# ArduinoFile_Schematic.net
KiCad netlist of a schematic drawn in EasyEDA
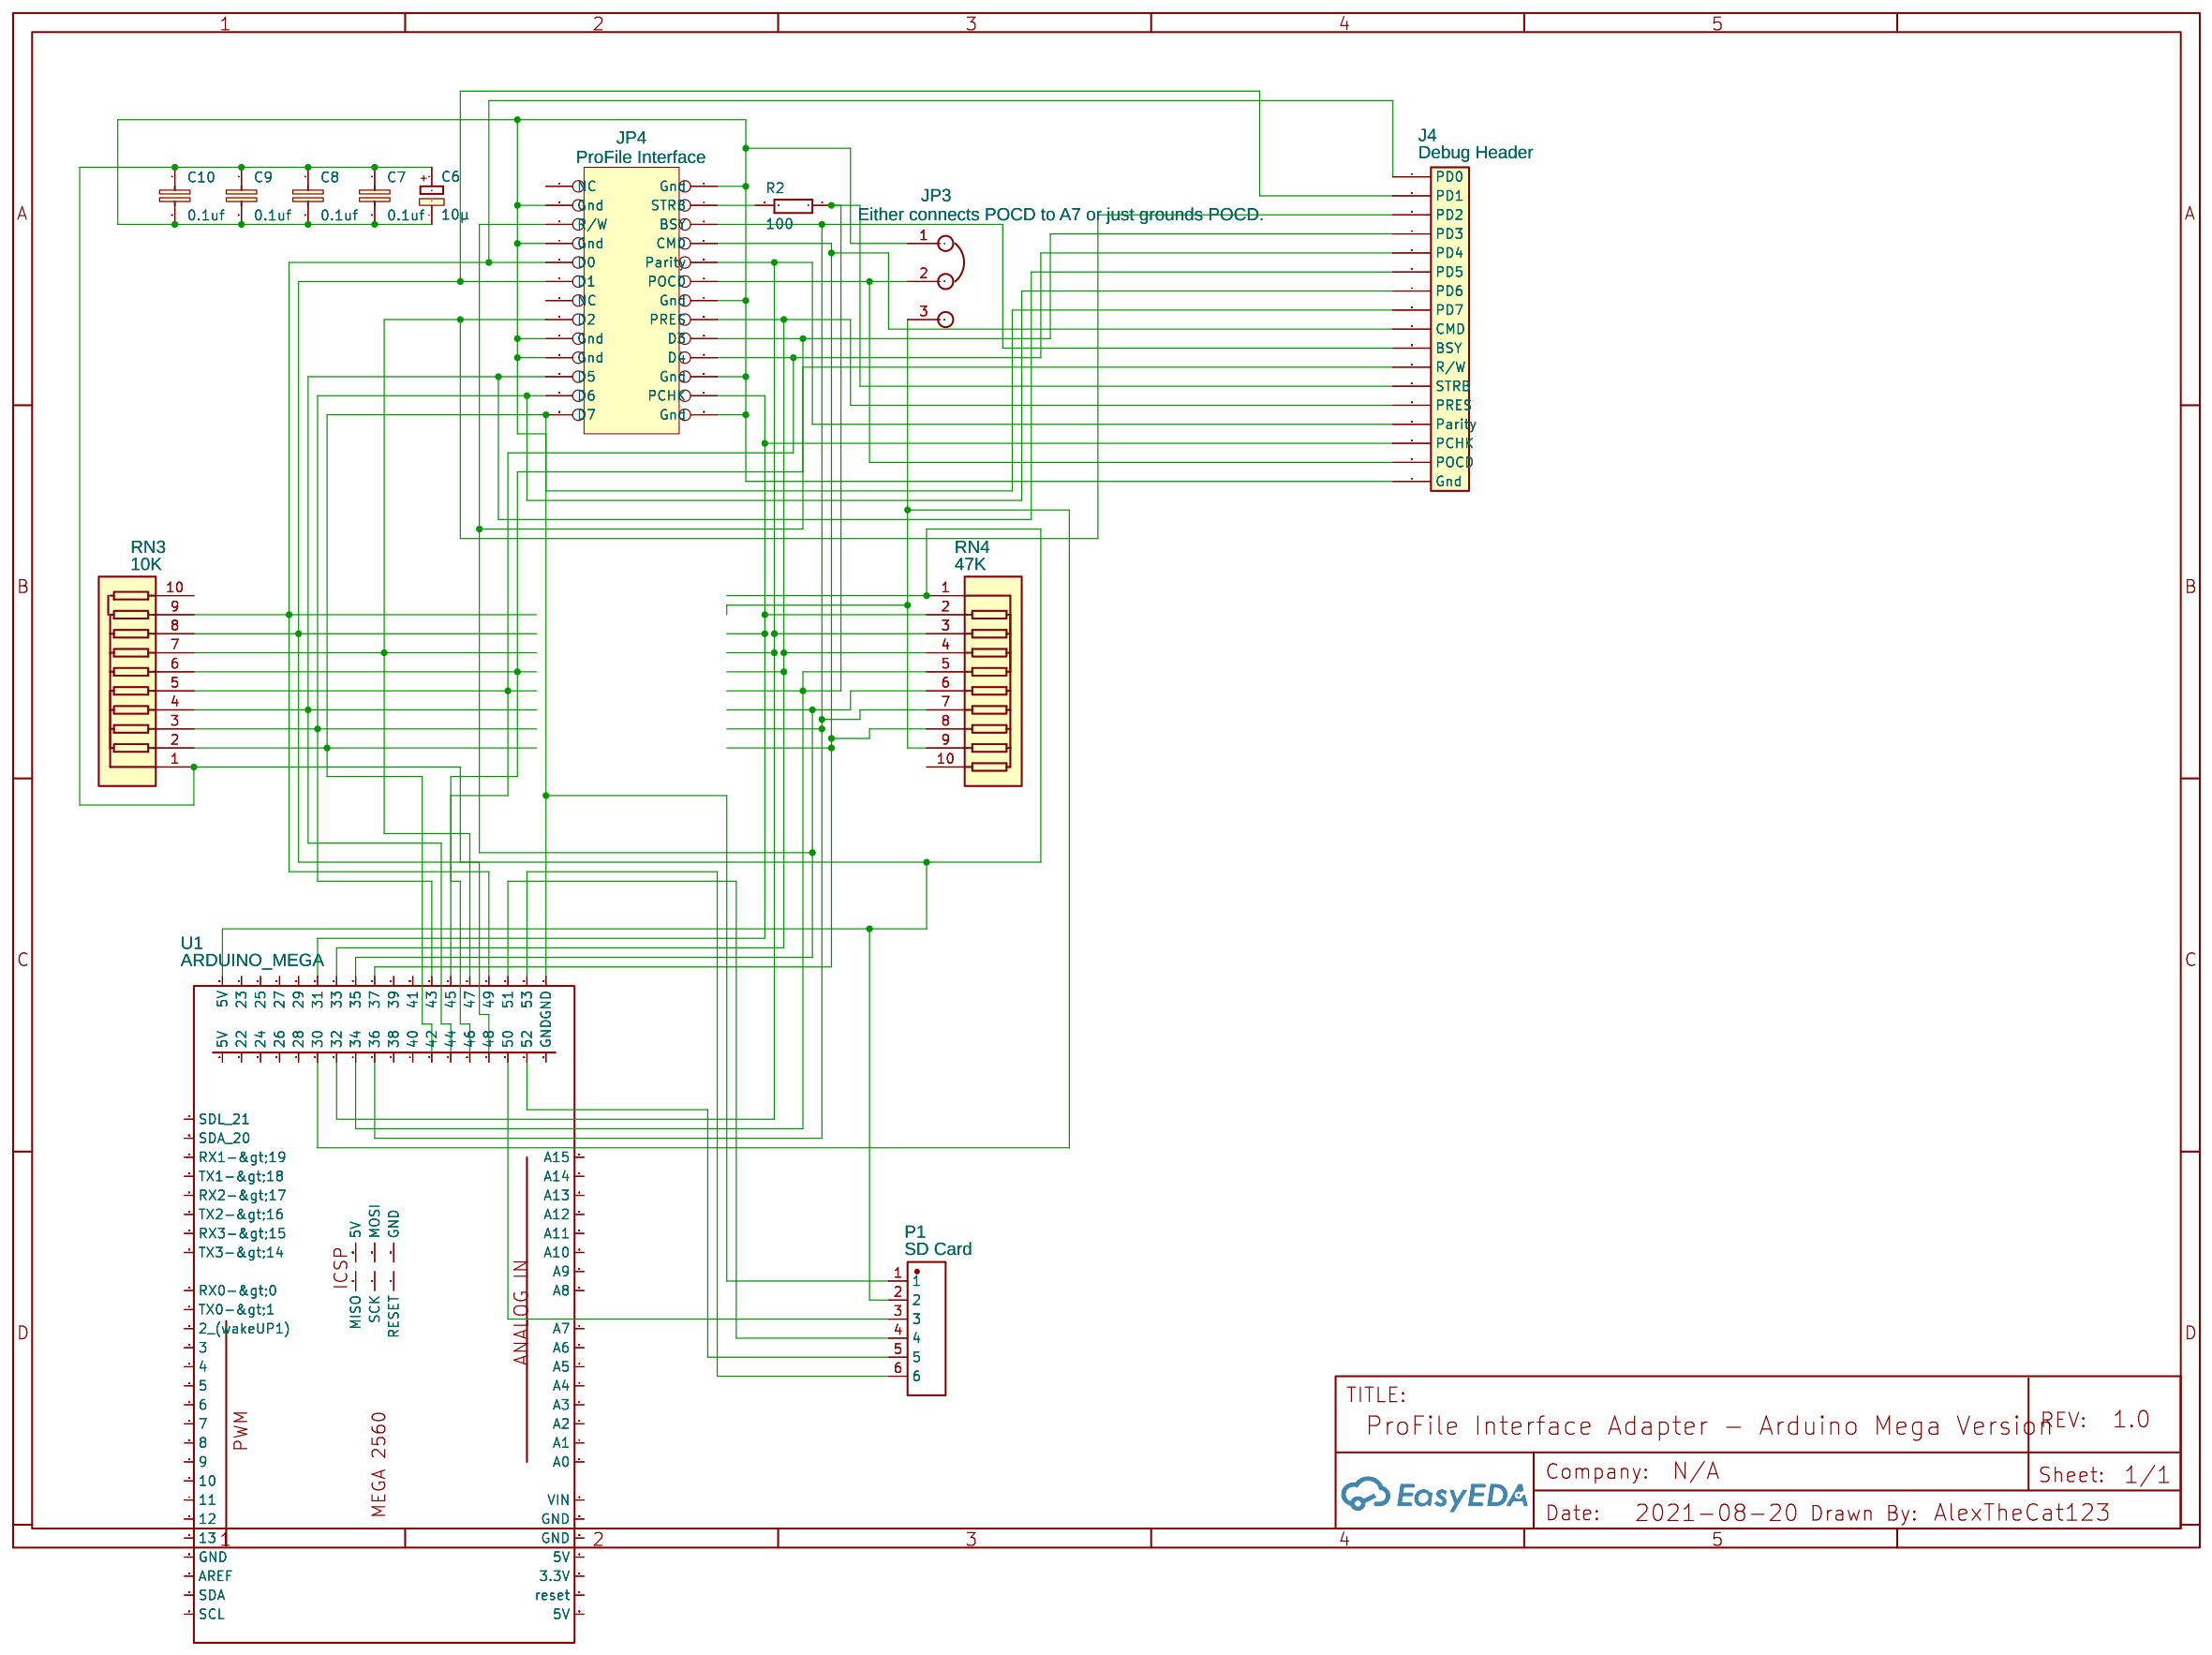
[diagram p0: schematic sheet]

(export (version "E")
  (design (tool "Eeschema 10.0.6"))
  (components
    (comp (ref "C6") (value "10µ") (libsource (lib "") (part "Unknown_220_-715")))
    (comp (ref "C7") (value "0.1uf") (libsource (lib "") (part "Unknown_190_-715")))
    (comp (ref "C8") (value "0.1uf") (libsource (lib "") (part "Unknown_155_-715")))
    (comp (ref "C9") (value "0.1uf") (libsource (lib "") (part "Unknown_120_-715")))
    (comp (ref "C10") (value "0.1uf") (libsource (lib "") (part "Unknown_85_-715")))
    (comp (ref "J4")
      (value "Debug Header")
      (fields
        (field (name "BOM_Manufacturer Part") "Header-2.54_1x17")
        (field (name "BOM_Supplier Part") "C52709")
      )
      (libsource (lib "") (part "Header-Female-2.54_1x17"))
    )
    (comp (ref "JP3")
      (value "Either connects POCD to A7 or just grounds POCD.")
      (libsource (lib "") (part "JUMPER"))
    )
    (comp (ref "JP4") (value "ProFile Interface") (libsource (lib "") (part "HEADER 13X2")))
    (comp (ref "P1")
      (value "SD Card")
      (fields
        (field (name "BOM_Manufacturer Part") "Female header 1*6p")
        (field (name "BOM_Supplier Part") "C40877")
      )
      (libsource (lib "") (part "Header-Female-2.54_1x6"))
    )
    (comp (ref "R2") (value "100") (libsource (lib "") (part "Unknown_410_-705")))
    (comp (ref "RN3")
      (value "10K")
      (fields (field (name "BOM_Manufacturer Part") "A09-202JP") (field (name "BOM_Supplier Part") "E84206"))
      (libsource (lib "") (part "1K_1"))
    )
    (comp (ref "RN4")
      (value "47K")
      (fields (field (name "BOM_Manufacturer Part") "A09-202JP") (field (name "BOM_Supplier Part") "E84206"))
      (libsource (lib "") (part "1K"))
    )
    (comp (ref "U1")
      (value "ARDUINO_MEGA")
      (fields (field (name "BOM_Manufacturer Part") "ARDUINO MEGA"))
      (libsource (lib "") (part "ARDUINO_MEGA"))
    )
  )
  (nets
    (net (code "1") (name "Net-(C10-Pad1)") (class "Default")
      (node (ref "C10") (pin "1") (pinfunction "1_1") (pintype "bidirectional"))
      (node (ref "C6") (pin "+") (pinfunction "+_+") (pintype "bidirectional"))
      (node (ref "C7") (pin "1") (pinfunction "1_1") (pintype "bidirectional"))
      (node (ref "C8") (pin "1") (pinfunction "1_1") (pintype "bidirectional"))
      (node (ref "C9") (pin "1") (pinfunction "1_1") (pintype "bidirectional"))
      (node (ref "P1") (pin "2") (pinfunction "2_2") (pintype "unspecified"))
      (node (ref "RN3") (pin "1") (pinfunction "1_1") (pintype "input"))
      (node (ref "RN4") (pin "1") (pinfunction "1_1") (pintype "input"))
      (node (ref "U1") (pin "5V..") (pinfunction "5V_5V..") (pintype "unspecified"))
    )
    (net (code "2") (name "Net-(J4-BSY)") (class "Default")
      (node (ref "J4") (pin "10") (pinfunction "BSY_10") (pintype "input"))
      (node (ref "JP4") (pin "6") (pinfunction "BSY_6") (pintype "unspecified"))
      (node (ref "RN4") (pin "7") (pinfunction "7_7") (pintype "input"))
      (node (ref "U1") (pin "43") (pinfunction "36_43") (pintype "unspecified"))
    )
    (net (code "3") (name "Net-(J4-CMD)") (class "Default")
      (node (ref "J4") (pin "9") (pinfunction "CMD_9") (pintype "input"))
      (node (ref "JP4") (pin "8") (pinfunction "CMD_8") (pintype "unspecified"))
      (node (ref "RN4") (pin "8") (pinfunction "8_8") (pintype "input"))
      (node (ref "U1") (pin "44") (pinfunction "37_44") (pintype "unspecified"))
    )
    (net (code "4") (name "Net-(J4-Gnd)") (class "Default")
      (node (ref "C10") (pin "2") (pinfunction "2_2") (pintype "bidirectional"))
      (node (ref "C6") (pin "-") (pinfunction "-_-") (pintype "bidirectional"))
      (node (ref "C7") (pin "2") (pinfunction "2_2") (pintype "bidirectional"))
      (node (ref "C8") (pin "2") (pinfunction "2_2") (pintype "bidirectional"))
      (node (ref "C9") (pin "2") (pinfunction "2_2") (pintype "bidirectional"))
      (node (ref "J4") (pin "17") (pinfunction "Gnd_17") (pintype "input"))
      (node (ref "JP3") (pin "1") (pinfunction "1_1") (pintype "unspecified"))
      (node (ref "JP4") (pin "14") (pinfunction "Gnd_14") (pintype "unspecified"))
      (node (ref "JP4") (pin "17") (pinfunction "Gnd_17") (pintype "unspecified"))
      (node (ref "JP4") (pin "19") (pinfunction "Gnd_19") (pintype "unspecified"))
      (node (ref "JP4") (pin "2") (pinfunction "Gnd_2") (pintype "unspecified"))
      (node (ref "JP4") (pin "22") (pinfunction "Gnd_22") (pintype "unspecified"))
      (node (ref "JP4") (pin "26") (pinfunction "Gnd_26") (pintype "unspecified"))
      (node (ref "JP4") (pin "3") (pinfunction "Gnd_3") (pintype "unspecified"))
      (node (ref "JP4") (pin "7") (pinfunction "Gnd_7") (pintype "unspecified"))
      (node (ref "P1") (pin "1") (pinfunction "1_1") (pintype "unspecified"))
      (node (ref "U1") (pin "GND") (pinfunction "GND_GND") (pintype "unspecified"))
    )
    (net (code "5") (name "Net-(J4-PCHK)") (class "Default")
      (node (ref "J4") (pin "15") (pinfunction "PCHK_15") (pintype "input"))
      (node (ref "JP4") (pin "24") (pinfunction "PCHK_24") (pintype "unspecified"))
      (node (ref "RN4") (pin "2") (pinfunction "2_2") (pintype "input"))
      (node (ref "U1") (pin "38") (pinfunction "31_38") (pintype "unspecified"))
    )
    (net (code "6") (name "Net-(J4-PD0)") (class "Default")
      (node (ref "J4") (pin "1") (pinfunction "PD0_1") (pintype "input"))
      (node (ref "JP4") (pin "9") (pinfunction "D0_9") (pintype "unspecified"))
      (node (ref "RN3") (pin "9") (pinfunction "9_9") (pintype "input"))
      (node (ref "U1") (pin "56") (pinfunction "49_56") (pintype "unspecified"))
    )
    (net (code "7") (name "Net-(J4-PD1)") (class "Default")
      (node (ref "J4") (pin "2") (pinfunction "PD1_2") (pintype "input"))
      (node (ref "JP4") (pin "11") (pinfunction "D1_11") (pintype "unspecified"))
      (node (ref "RN3") (pin "8") (pinfunction "8_8") (pintype "input"))
      (node (ref "U1") (pin "55") (pinfunction "48_55") (pintype "unspecified"))
    )
    (net (code "8") (name "Net-(J4-PD2)") (class "Default")
      (node (ref "J4") (pin "3") (pinfunction "PD2_3") (pintype "input"))
      (node (ref "JP4") (pin "15") (pinfunction "D2_15") (pintype "unspecified"))
      (node (ref "RN3") (pin "7") (pinfunction "7_7") (pintype "input"))
      (node (ref "U1") (pin "54") (pinfunction "47_54") (pintype "unspecified"))
    )
    (net (code "9") (name "Net-(J4-PD3)") (class "Default")
      (node (ref "J4") (pin "4") (pinfunction "PD3_4") (pintype "input"))
      (node (ref "JP4") (pin "18") (pinfunction "D3_18") (pintype "unspecified"))
      (node (ref "RN3") (pin "6") (pinfunction "6_6") (pintype "input"))
      (node (ref "U1") (pin "53") (pinfunction "46_53") (pintype "unspecified"))
    )
    (net (code "10") (name "Net-(J4-PD4)") (class "Default")
      (node (ref "J4") (pin "5") (pinfunction "PD4_5") (pintype "input"))
      (node (ref "JP4") (pin "20") (pinfunction "D4_20") (pintype "unspecified"))
      (node (ref "RN3") (pin "5") (pinfunction "5_5") (pintype "input"))
      (node (ref "U1") (pin "52") (pinfunction "45_52") (pintype "unspecified"))
    )
    (net (code "11") (name "Net-(J4-PD5)") (class "Default")
      (node (ref "J4") (pin "6") (pinfunction "PD5_6") (pintype "input"))
      (node (ref "JP4") (pin "21") (pinfunction "D5_21") (pintype "unspecified"))
      (node (ref "RN3") (pin "4") (pinfunction "4_4") (pintype "input"))
      (node (ref "U1") (pin "51") (pinfunction "44_51") (pintype "unspecified"))
    )
    (net (code "12") (name "Net-(J4-PD6)") (class "Default")
      (node (ref "J4") (pin "7") (pinfunction "PD6_7") (pintype "input"))
      (node (ref "JP4") (pin "23") (pinfunction "D6_23") (pintype "unspecified"))
      (node (ref "RN3") (pin "3") (pinfunction "3_3") (pintype "input"))
      (node (ref "U1") (pin "50") (pinfunction "43_50") (pintype "unspecified"))
    )
    (net (code "13") (name "Net-(J4-PD7)") (class "Default")
      (node (ref "J4") (pin "8") (pinfunction "PD7_8") (pintype "input"))
      (node (ref "JP4") (pin "25") (pinfunction "D7_25") (pintype "unspecified"))
      (node (ref "RN3") (pin "2") (pinfunction "2_2") (pintype "input"))
    )
    (net (code "14") (name "Net-(J4-POCD)") (class "Default")
      (node (ref "J4") (pin "16") (pinfunction "POCD_16") (pintype "input"))
      (node (ref "JP3") (pin "2") (pinfunction "2_2") (pintype "unspecified"))
      (node (ref "JP4") (pin "12") (pinfunction "POCD_12") (pintype "unspecified"))
    )
    (net (code "15") (name "Net-(J4-PRES)") (class "Default")
      (node (ref "J4") (pin "13") (pinfunction "PRES_13") (pintype "input"))
      (node (ref "JP4") (pin "16") (pinfunction "PRES_16") (pintype "unspecified"))
      (node (ref "RN4") (pin "4") (pinfunction "4_4") (pintype "input"))
      (node (ref "U1") (pin "40") (pinfunction "33_40") (pintype "unspecified"))
    )
    (net (code "16") (name "Net-(J4-Parity)") (class "Default")
      (node (ref "J4") (pin "14") (pinfunction "Parity_14") (pintype "input"))
      (node (ref "JP4") (pin "10") (pinfunction "Parity_10") (pintype "unspecified"))
      (node (ref "RN4") (pin "3") (pinfunction "3_3") (pintype "input"))
      (node (ref "U1") (pin "39") (pinfunction "32_39") (pintype "unspecified"))
    )
    (net (code "17") (name "Net-(J4-R{slash}W)") (class "Default")
      (node (ref "J4") (pin "11") (pinfunction "R/W_11") (pintype "input"))
      (node (ref "JP4") (pin "5") (pinfunction "R/W_5") (pintype "unspecified"))
      (node (ref "RN4") (pin "6") (pinfunction "6_6") (pintype "input"))
      (node (ref "U1") (pin "42") (pinfunction "35_42") (pintype "unspecified"))
    )
    (net (code "18") (name "Net-(J4-STRB)") (class "Default")
      (node (ref "J4") (pin "12") (pinfunction "STRB_12") (pintype "input"))
      (node (ref "R2") (pin "2") (pinfunction "2_2") (pintype "bidirectional"))
      (node (ref "RN4") (pin "5") (pinfunction "5_5") (pintype "input"))
      (node (ref "U1") (pin "41") (pinfunction "34_41") (pintype "unspecified"))
    )
    (net (code "19") (name "Net-(JP4-STRB)") (class "Default")
      (node (ref "JP4") (pin "4") (pinfunction "STRB_4") (pintype "unspecified"))
      (node (ref "R2") (pin "1") (pinfunction "1_1") (pintype "bidirectional"))
    )
    (net (code "20") (name "Net-(U1-30)") (class "Default")
      (node (ref "JP3") (pin "3") (pinfunction "2_3") (pintype "unspecified"))
      (node (ref "RN4") (pin "9") (pinfunction "9_9") (pintype "input"))
      (node (ref "U1") (pin "37") (pinfunction "30_37") (pintype "unspecified"))
    )
    (net (code "21") (name "Net-(U1-50)") (class "Default")
      (node (ref "P1") (pin "3") (pinfunction "3_3") (pintype "unspecified"))
      (node (ref "U1") (pin "57") (pinfunction "50_57") (pintype "unspecified"))
    )
    (net (code "22") (name "Net-(U1-51)") (class "Default")
      (node (ref "P1") (pin "4") (pinfunction "4_4") (pintype "unspecified"))
      (node (ref "U1") (pin "58") (pinfunction "51_58") (pintype "unspecified"))
    )
    (net (code "23") (name "Net-(U1-52)") (class "Default")
      (node (ref "P1") (pin "5") (pinfunction "5_5") (pintype "unspecified"))
      (node (ref "U1") (pin "59") (pinfunction "52_59") (pintype "unspecified"))
    )
    (net (code "24") (name "Net-(U1-53)") (class "Default")
      (node (ref "P1") (pin "6") (pinfunction "6_6") (pintype "unspecified"))
      (node (ref "U1") (pin "60") (pinfunction "53_60") (pintype "unspecified"))
    )
    (net (code "25") (name "unconnected-(JP4-NC-Pad1)") (class "Default")
      (node (ref "JP4") (pin "1") (pinfunction "NC_1") (pintype "unspecified"))
    )
    (net (code "26") (name "unconnected-(JP4-NC-Pad13)") (class "Default")
      (node (ref "JP4") (pin "13") (pinfunction "NC_13") (pintype "unspecified"))
    )
    (net (code "27") (name "unconnected-(RN3-9-Pad10)") (class "Default")
      (node (ref "RN3") (pin "10") (pinfunction "9_10") (pintype "input"))
    )
    (net (code "28") (name "unconnected-(RN4-9-Pad10)") (class "Default")
      (node (ref "RN4") (pin "10") (pinfunction "9_10") (pintype "input"))
    )
    (net (code "29") (name "unconnected-(U1-2_(wakeUP1)-Pad16)") (class "Default")
      (node (ref "U1") (pin "16") (pinfunction "2_(wakeUP1)_16") (pintype "unspecified"))
    )
    (net (code "30") (name "unconnected-(U1-3-Pad15)") (class "Default")
      (node (ref "U1") (pin "15") (pinfunction "3_15") (pintype "unspecified"))
    )
    (net (code "31") (name "unconnected-(U1-3.3V-Pad83)") (class "Default")
      (node (ref "U1") (pin "83") (pinfunction "3.3V_83") (pintype "unspecified"))
    )
    (net (code "32") (name "unconnected-(U1-4-Pad14)") (class "Default")
      (node (ref "U1") (pin "14") (pinfunction "4_14") (pintype "unspecified"))
    )
    (net (code "33") (name "unconnected-(U1-5-Pad13)") (class "Default")
      (node (ref "U1") (pin "13") (pinfunction "5_13") (pintype "unspecified"))
    )
    (net (code "34") (name "unconnected-(U1-5V-Pad5V.)") (class "Default")
      (node (ref "U1") (pin "5V.") (pinfunction "5V_5V.") (pintype "unspecified"))
    )
    (net (code "35") (name "unconnected-(U1-5V-Pad5V...)") (class "Default")
      (node (ref "U1") (pin "5V...") (pinfunction "5V_5V...") (pintype "unspecified"))
    )
    (net (code "36") (name "unconnected-(U1-5V-Pad5VICSP)") (class "Default")
      (node (ref "U1") (pin "5VICSP") (pinfunction "5V_5VICSP") (pintype "unspecified"))
    )
    (net (code "37") (name "unconnected-(U1-6-Pad12)") (class "Default")
      (node (ref "U1") (pin "12") (pinfunction "6_12") (pintype "unspecified"))
    )
    (net (code "38") (name "unconnected-(U1-7-Pad11)") (class "Default")
      (node (ref "U1") (pin "11") (pinfunction "7_11") (pintype "unspecified"))
    )
    (net (code "39") (name "unconnected-(U1-8-Pad10)") (class "Default")
      (node (ref "U1") (pin "10") (pinfunction "8_10") (pintype "unspecified"))
    )
    (net (code "40") (name "unconnected-(U1-10-Pad8)") (class "Default")
      (node (ref "U1") (pin "8") (pinfunction "10_8") (pintype "unspecified"))
    )
    (net (code "41") (name "unconnected-(U1-11-Pad7)") (class "Default")
      (node (ref "U1") (pin "7") (pinfunction "11_7") (pintype "unspecified"))
    )
    (net (code "42") (name "unconnected-(U1-12-Pad6)") (class "Default")
      (node (ref "U1") (pin "6") (pinfunction "12_6") (pintype "unspecified"))
    )
    (net (code "43") (name "unconnected-(U1-13-Pad5)") (class "Default")
      (node (ref "U1") (pin "5") (pinfunction "13_5") (pintype "unspecified"))
    )
    (net (code "44") (name "unconnected-(U1-22-Pad29)") (class "Default")
      (node (ref "U1") (pin "29") (pinfunction "22_29") (pintype "unspecified"))
    )
    (net (code "45") (name "unconnected-(U1-23-Pad30)") (class "Default")
      (node (ref "U1") (pin "30") (pinfunction "23_30") (pintype "unspecified"))
    )
    (net (code "46") (name "unconnected-(U1-24-Pad31)") (class "Default")
      (node (ref "U1") (pin "31") (pinfunction "24_31") (pintype "unspecified"))
    )
    (net (code "47") (name "unconnected-(U1-25-Pad32)") (class "Default")
      (node (ref "U1") (pin "32") (pinfunction "25_32") (pintype "unspecified"))
    )
    (net (code "48") (name "unconnected-(U1-26-Pad33)") (class "Default")
      (node (ref "U1") (pin "33") (pinfunction "26_33") (pintype "unspecified"))
    )
    (net (code "49") (name "unconnected-(U1-27-Pad34)") (class "Default")
      (node (ref "U1") (pin "34") (pinfunction "27_34") (pintype "unspecified"))
    )
    (net (code "50") (name "unconnected-(U1-28-Pad35)") (class "Default")
      (node (ref "U1") (pin "35") (pinfunction "28_35") (pintype "unspecified"))
    )
    (net (code "51") (name "unconnected-(U1-29-Pad36)") (class "Default")
      (node (ref "U1") (pin "36") (pinfunction "29_36") (pintype "unspecified"))
    )
    (net (code "52") (name "unconnected-(U1-38-Pad45)") (class "Default")
      (node (ref "U1") (pin "45") (pinfunction "38_45") (pintype "unspecified"))
    )
    (net (code "53") (name "unconnected-(U1-39-Pad46)") (class "Default")
      (node (ref "U1") (pin "46") (pinfunction "39_46") (pintype "unspecified"))
    )
    (net (code "54") (name "unconnected-(U1-40-Pad47)") (class "Default")
      (node (ref "U1") (pin "47") (pinfunction "40_47") (pintype "unspecified"))
    )
    (net (code "55") (name "unconnected-(U1-41-Pad48)") (class "Default")
      (node (ref "U1") (pin "48") (pinfunction "41_48") (pintype "unspecified"))
    )
    (net (code "56") (name "unconnected-(U1-42-Pad49)") (class "Default")
      (node (ref "U1") (pin "49") (pinfunction "42_49") (pintype "unspecified"))
    )
    (net (code "57") (name "unconnected-(U1-A0-Pad78)") (class "Default")
      (node (ref "U1") (pin "78") (pinfunction "A0_78") (pintype "unspecified"))
    )
    (net (code "58") (name "unconnected-(U1-A1-Pad77)") (class "Default")
      (node (ref "U1") (pin "77") (pinfunction "A1_77") (pintype "unspecified"))
    )
    (net (code "59") (name "unconnected-(U1-A2-Pad76)") (class "Default")
      (node (ref "U1") (pin "76") (pinfunction "A2_76") (pintype "unspecified"))
    )
    (net (code "60") (name "unconnected-(U1-A3-Pad75)") (class "Default")
      (node (ref "U1") (pin "75") (pinfunction "A3_75") (pintype "unspecified"))
    )
    (net (code "61") (name "unconnected-(U1-A4-Pad74)") (class "Default")
      (node (ref "U1") (pin "74") (pinfunction "A4_74") (pintype "unspecified"))
    )
    (net (code "62") (name "unconnected-(U1-A5-Pad73)") (class "Default")
      (node (ref "U1") (pin "73") (pinfunction "A5_73") (pintype "unspecified"))
    )
    (net (code "63") (name "unconnected-(U1-A6-Pad72)") (class "Default")
      (node (ref "U1") (pin "72") (pinfunction "A6_72") (pintype "unspecified"))
    )
    (net (code "64") (name "unconnected-(U1-A7-Pad71)") (class "Default")
      (node (ref "U1") (pin "71") (pinfunction "A7_71") (pintype "unspecified"))
    )
    (net (code "65") (name "unconnected-(U1-A8-Pad70)") (class "Default")
      (node (ref "U1") (pin "70") (pinfunction "A8_70") (pintype "unspecified"))
    )
    (net (code "66") (name "unconnected-(U1-A9-Pad69)") (class "Default")
      (node (ref "U1") (pin "69") (pinfunction "A9_69") (pintype "unspecified"))
    )
    (net (code "67") (name "unconnected-(U1-A10-Pad68)") (class "Default")
      (node (ref "U1") (pin "68") (pinfunction "A10_68") (pintype "unspecified"))
    )
    (net (code "68") (name "unconnected-(U1-A11-Pad67)") (class "Default")
      (node (ref "U1") (pin "67") (pinfunction "A11_67") (pintype "unspecified"))
    )
    (net (code "69") (name "unconnected-(U1-A12-Pad66)") (class "Default")
      (node (ref "U1") (pin "66") (pinfunction "A12_66") (pintype "unspecified"))
    )
    (net (code "70") (name "unconnected-(U1-A13-Pad65)") (class "Default")
      (node (ref "U1") (pin "65") (pinfunction "A13_65") (pintype "unspecified"))
    )
    (net (code "71") (name "unconnected-(U1-A14-Pad64)") (class "Default")
      (node (ref "U1") (pin "64") (pinfunction "A14_64") (pintype "unspecified"))
    )
    (net (code "72") (name "unconnected-(U1-A15-Pad63)") (class "Default")
      (node (ref "U1") (pin "63") (pinfunction "A15_63") (pintype "unspecified"))
    )
    (net (code "73") (name "unconnected-(U1-AREF-Pad3)") (class "Default")
      (node (ref "U1") (pin "3") (pinfunction "AREF_3") (pintype "unspecified"))
    )
    (net (code "74") (name "unconnected-(U1-MISO-Pad86)") (class "Default")
      (node (ref "U1") (pin "86") (pinfunction "MISO_86") (pintype "unspecified"))
    )
    (net (code "75") (name "unconnected-(U1-MOSI-Pad90)") (class "Default")
      (node (ref "U1") (pin "90") (pinfunction "MOSI_90") (pintype "unspecified"))
    )
    (net (code "76") (name "unconnected-(U1-Pad5V)") (class "Default")
      (node (ref "U1") (pin "5V") (pinfunction "5V_5V") (pintype "unspecified"))
    )
    (net (code "77") (name "unconnected-(U1-Pad9)") (class "Default")
      (node (ref "U1") (pin "9") (pinfunction "9_9") (pintype "unspecified"))
    )
    (net (code "78") (name "unconnected-(U1-PadGND)") (class "Default")
      (node (ref "U1") (pin "GND") (pinfunction "GND_GND") (pintype "unspecified"))
    )
    (net (code "79") (name "unconnected-(U1-PadGND)_1") (class "Default")
      (node (ref "U1") (pin "GND") (pinfunction "GND_GND") (pintype "unspecified"))
    )
    (net (code "80") (name "unconnected-(U1-PadGND)_2") (class "Default")
      (node (ref "U1") (pin "GND") (pinfunction "GND_GND") (pintype "unspecified"))
    )
    (net (code "81") (name "unconnected-(U1-PadGND)_3") (class "Default")
      (node (ref "U1") (pin "GND") (pinfunction "GND_GND") (pintype "unspecified"))
    )
    (net (code "82") (name "unconnected-(U1-PadGND)_4") (class "Default")
      (node (ref "U1") (pin "GND") (pinfunction "GND_GND") (pintype "unspecified"))
    )
    (net (code "83") (name "unconnected-(U1-PadSCL)") (class "Default")
      (node (ref "U1") (pin "SCL") (pinfunction "SCL_SCL") (pintype "unspecified"))
    )
    (net (code "84") (name "unconnected-(U1-PadSDA)") (class "Default")
      (node (ref "U1") (pin "SDA") (pinfunction "SDA_SDA") (pintype "unspecified"))
    )
    (net (code "85") (name "unconnected-(U1-PadVIN)") (class "Default")
      (node (ref "U1") (pin "VIN") (pinfunction "VIN_VIN") (pintype "unspecified"))
    )
    (net (code "86") (name "unconnected-(U1-RESET-Pad88)") (class "Default")
      (node (ref "U1") (pin "88") (pinfunction "RESET_88") (pintype "unspecified"))
    )
    (net (code "87") (name "unconnected-(U1-RX0-&gt;0-Pad18)") (class "Default")
      (node (ref "U1") (pin "18") (pinfunction "RX0-&gt;0_18") (pintype "unspecified"))
    )
    (net (code "88") (name "unconnected-(U1-RX1-&gt;19-Pad24)") (class "Default")
      (node (ref "U1") (pin "24") (pinfunction "RX1-&gt;19_24") (pintype "unspecified"))
    )
    (net (code "89") (name "unconnected-(U1-RX2-&gt;17-Pad22)") (class "Default")
      (node (ref "U1") (pin "22") (pinfunction "RX2-&gt;17_22") (pintype "unspecified"))
    )
    (net (code "90") (name "unconnected-(U1-RX3-&gt;15-Pad20)") (class "Default")
      (node (ref "U1") (pin "20") (pinfunction "RX3-&gt;15_20") (pintype "unspecified"))
    )
    (net (code "91") (name "unconnected-(U1-SCK-Pad87)") (class "Default")
      (node (ref "U1") (pin "87") (pinfunction "SCK_87") (pintype "unspecified"))
    )
    (net (code "92") (name "unconnected-(U1-SDA_20-PadSDA2)") (class "Default")
      (node (ref "U1") (pin "SDA2") (pinfunction "SDA_20_SDA2") (pintype "unspecified"))
    )
    (net (code "93") (name "unconnected-(U1-SDL_21-PadSCL2)") (class "Default")
      (node (ref "U1") (pin "SCL2") (pinfunction "SDL_21_SCL2") (pintype "unspecified"))
    )
    (net (code "94") (name "unconnected-(U1-TX0-&gt;1-Pad17)") (class "Default")
      (node (ref "U1") (pin "17") (pinfunction "TX0-&gt;1_17") (pintype "unspecified"))
    )
    (net (code "95") (name "unconnected-(U1-TX1-&gt;18-Pad23)") (class "Default")
      (node (ref "U1") (pin "23") (pinfunction "TX1-&gt;18_23") (pintype "unspecified"))
    )
    (net (code "96") (name "unconnected-(U1-TX2-&gt;16-Pad21)") (class "Default")
      (node (ref "U1") (pin "21") (pinfunction "TX2-&gt;16_21") (pintype "unspecified"))
    )
    (net (code "97") (name "unconnected-(U1-TX3-&gt;14-Pad19)") (class "Default")
      (node (ref "U1") (pin "19") (pinfunction "TX3-&gt;14_19") (pintype "unspecified"))
    )
    (net (code "98") (name "unconnected-(U1-reset-Pad84)") (class "Default")
      (node (ref "U1") (pin "84") (pinfunction "reset_84") (pintype "unspecified"))
    )
  )
)
